# GPS_WATHER_STATION.net
KiCad netlist of a schematic drawn in Altium Designer
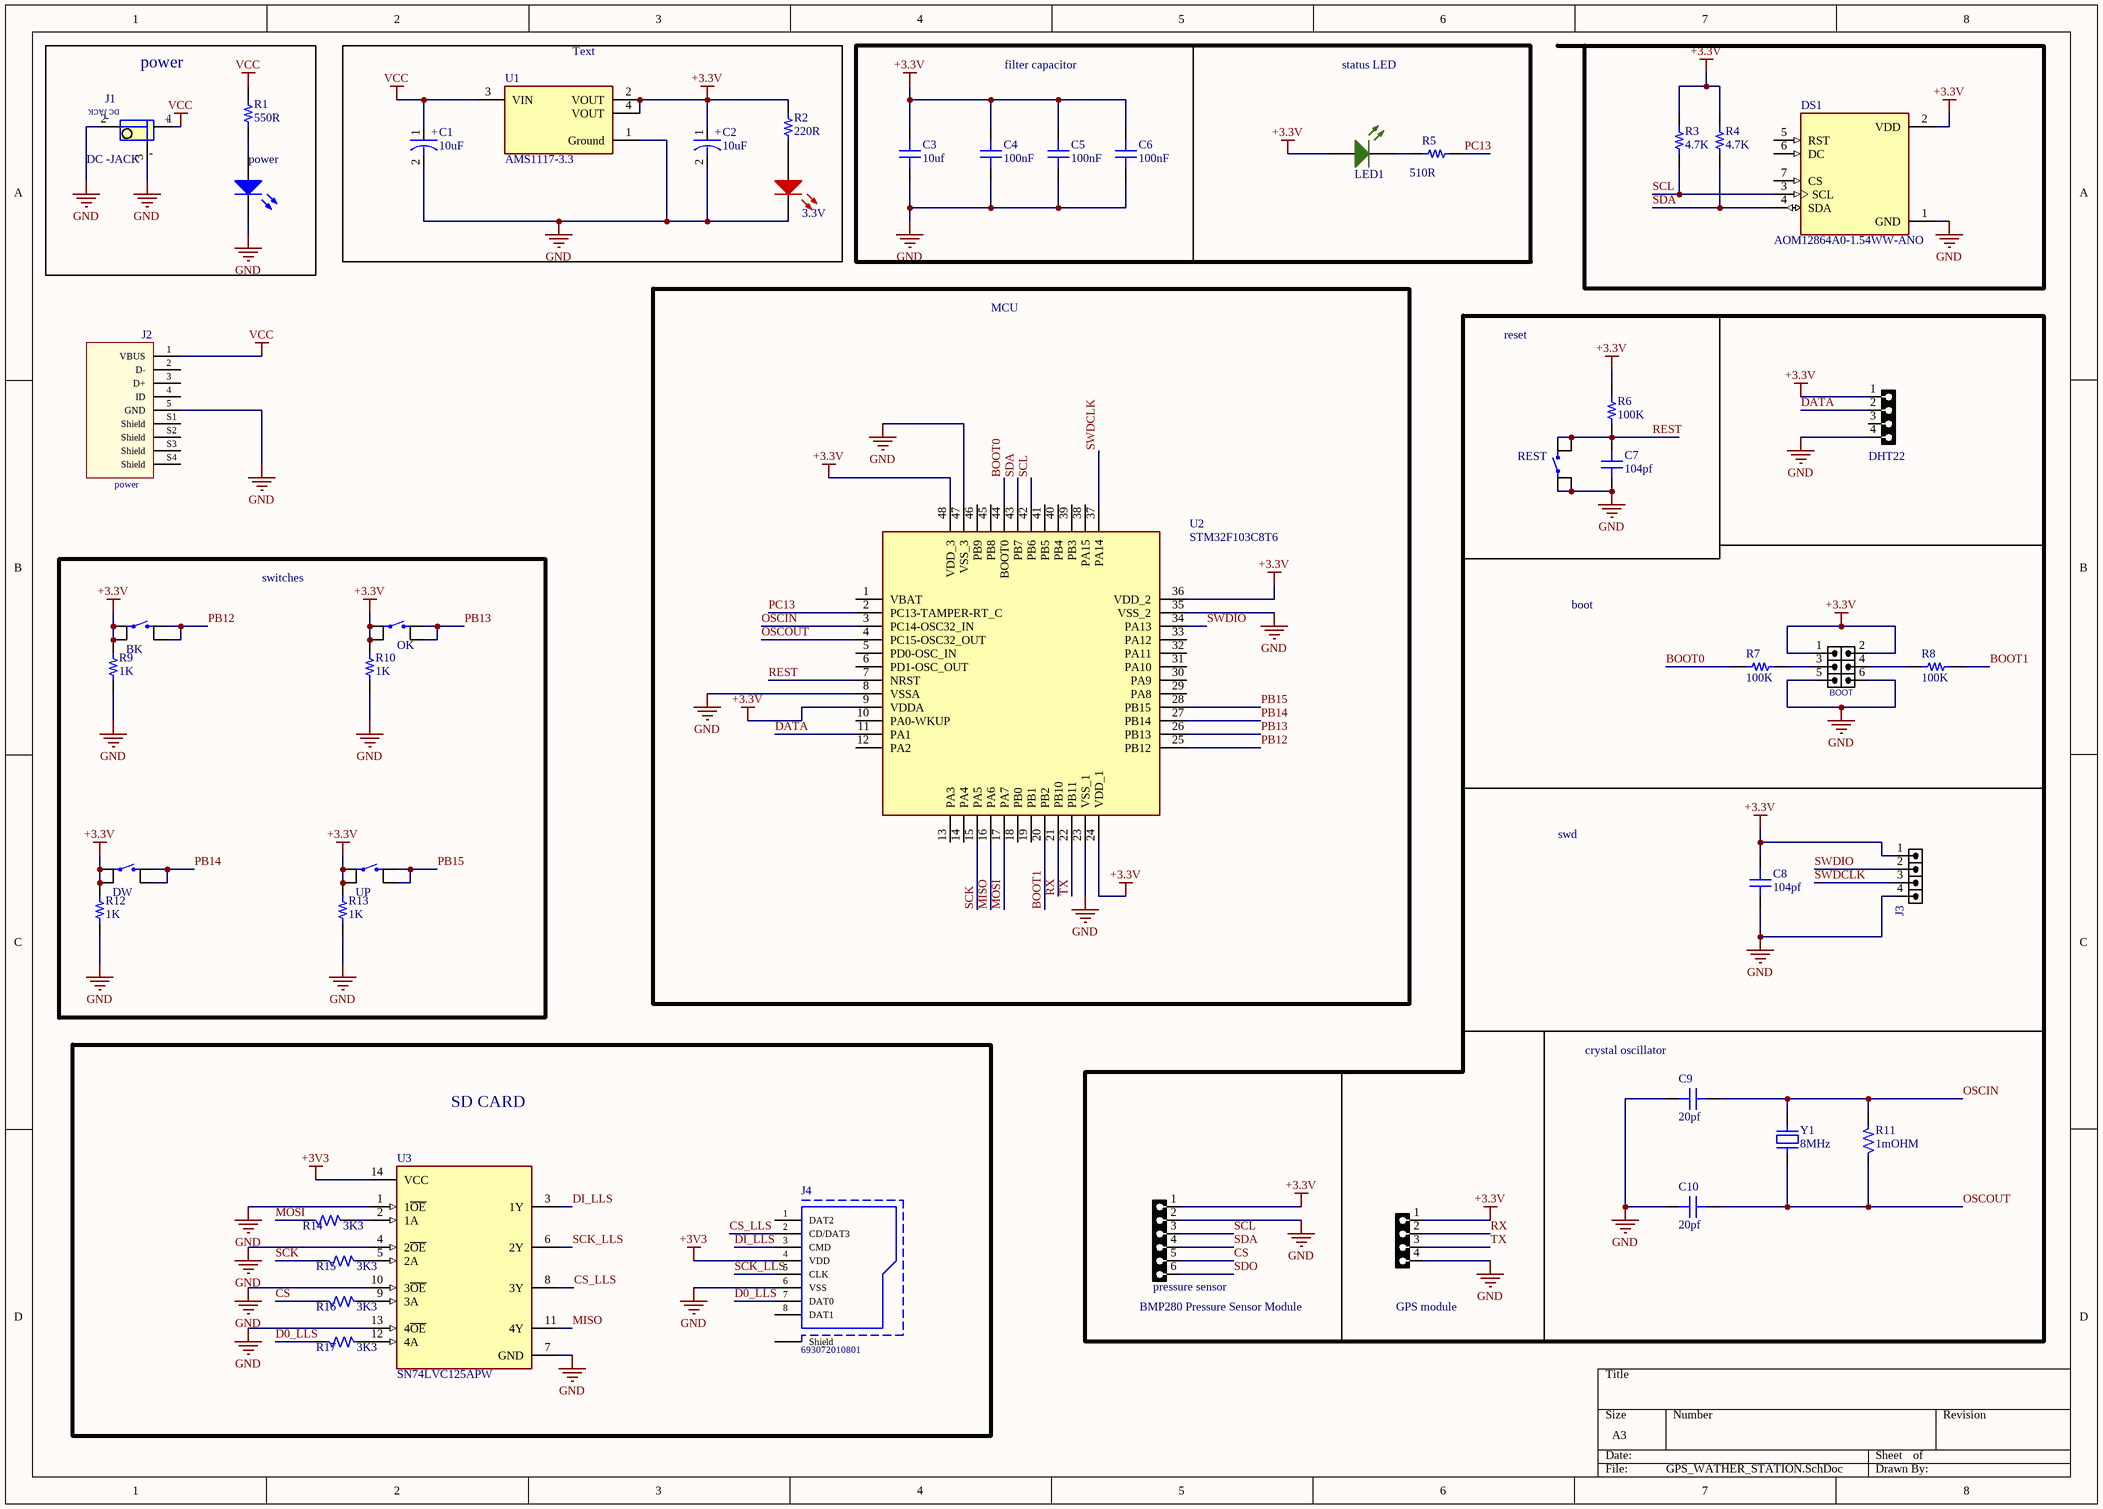
[diagram p0: GPS_WATHER_STATION.SchDoc]

(export (version "E")
  (design (tool "Eeschema 10.0.6"))
  (components
    (comp (ref "3.3V")
      (value "LED SMD 0603 RED")
      (footprint "LED_0603_BLUE")
      (libsource (lib "Led") (part "LED SMD 0603 RED"))
    )
    (comp (ref "BK")
      (value "Tactile 4PIN 6X6mm H4.5mm (SMD)")
      (footprint "SWPBS_SPDT_6X6X5")
      (description "Tactile Switch SPST-NO Top Actuated Surface Mount")
      (fields (field (name "PARTNUMBER") "PTS645SM43SMTR92 LFS"))
      (libsource (lib "Switch") (part "Tactile 4PIN 6X6mm H4.5mm (SMD)"))
    )
    (comp (ref "BOOT")
      (value "HDRM_2X3")
      (footprint "HDRS_M_2X3")
      (description "CONN, HEADER, Male, pitch: 2.54mm, 6POS, SMD")
      (fields (field (name "MANF_P#") "MANF_PART#") (field (name "MANF") "MANF"))
      (libsource (lib "Conn Header") (part "HDRS_M_2X3"))
    )
    (comp (ref "C1")
      (value "10uF")
      (footprint "CAP-T_1206")
      (description "10µF Molded Tantalum Capacitors 16V 1206 (3216 Metric) 3Ohm")
      (fields
        (field (name "MANUFACTURER") "AVX Corporation")
        (field (name "MANUFACTURER PART NUMBER") "TAJA106K016SNJ")
      )
      (libsource (lib "ESTEEMPCBLIB") (part "CAP-P_10uF-16V-10%-1206"))
    )
    (comp (ref "C2")
      (value "10uF")
      (footprint "CAP-T_1206")
      (description "10µF Molded Tantalum Capacitors 16V 1206 (3216 Metric) 3Ohm")
      (fields
        (field (name "MANUFACTURER") "AVX Corporation")
        (field (name "MANUFACTURER PART NUMBER") "TAJA106K016SNJ")
      )
      (libsource (lib "ESTEEMPCBLIB") (part "CAP-P_10uF-16V-10%-1206"))
    )
    (comp (ref "C3")
      (value "10uf")
      (footprint "CAP 0402_1005")
      (description "SMT Capacitor")
      (libsource (lib "Capacitor") (part "Cap 0402"))
    )
    (comp (ref "C4")
      (value "100nF")
      (footprint "CAP 0402_1005")
      (description "SMT Capacitor")
      (libsource (lib "Capacitor") (part "Cap 0402"))
    )
    (comp (ref "C5")
      (value "100nF")
      (footprint "CAP 0402_1005")
      (description "SMT Capacitor")
      (libsource (lib "Capacitor") (part "Cap 0402"))
    )
    (comp (ref "C6")
      (value "100nF")
      (footprint "CAP 0402_1005")
      (description "SMT Capacitor")
      (libsource (lib "Capacitor") (part "Cap 0402"))
    )
    (comp (ref "C7")
      (value "104pf")
      (footprint "CAP 0402_1005")
      (description "SMT Capacitor")
      (libsource (lib "Capacitor") (part "Cap 0402"))
    )
    (comp (ref "C8")
      (value "104pf")
      (footprint "CAP 0402_1005")
      (description "SMT Capacitor")
      (libsource (lib "Capacitor") (part "Cap 0402"))
    )
    (comp (ref "C9")
      (value "20pf")
      (footprint "CAP 0402_1005")
      (description "SMT Capacitor")
      (libsource (lib "Capacitor") (part "Cap 0402"))
    )
    (comp (ref "C10")
      (value "20pf")
      (footprint "CAP 0402_1005")
      (description "SMT Capacitor")
      (libsource (lib "Capacitor") (part "Cap 0402"))
    )
    (comp (ref "DHT22")
      (value "HDRF4")
      (footprint "HDRLP_F_1X4")
      (description "CONN, HEADER, Male, pitch: 2.54mm, 4POS")
      (libsource (lib "") (part "HDRLP_F_1X4_1"))
    )
    (comp (ref "DS1")
      (value "AOM12864A0-1.54WW-ANO")
      (footprint "LCD_AOM12864A0-1.54WW-ANO")
      (description "Non-Touch Graphic LCD Display Module - White OLED SPI 1.54 (39.12mm) 128 x 64")
      (fields (field (name "MF") "Orient Display"))
      (libsource (lib "AOM12864A0-1.54WW-ANO") (part "AOM12864A0-1.54WW-ANO"))
    )
    (comp (ref "DW")
      (value "Tactile 4PIN 6X6mm H4.5mm (SMD)")
      (footprint "SWPBS_SPDT_6X6X5")
      (description "Tactile Switch SPST-NO Top Actuated Surface Mount")
      (fields (field (name "PARTNUMBER") "PTS645SM43SMTR92 LFS"))
      (libsource (lib "Switch") (part "Tactile 4PIN 6X6mm H4.5mm (SMD)"))
    )
    (comp (ref "GPS module")
      (value "HDRF4")
      (footprint "HDRLP_F_1X4")
      (description "CONN, HEADER, Male, pitch: 2.54mm, 4POS")
      (libsource (lib "Conn Header") (part "HDRLP_F_1X4"))
    )
    (comp (ref "J1")
      (value "DC -JACK")
      (footprint "CON3_129_PJ-002A_TH_RA")
      (description "3 Pins, 1 Row 228mil Pitch, right angle Connector, male")
      (fields (field (name "MANUFACTURER") "JST") (field (name "MANUFACTURER PART NUMBER") "PJ-002A"))
      (libsource (lib "ESTEEMPCBLIB") (part "CON-PLG_3X1-228-DC_JACK"))
    )
    (comp (ref "J2")
      (value "power")
      (footprint "629105150521")
      (description "Micro USB 2.0 Type B Horizontal SMT 5 Contacts High Current WR-COM")
      (fields (field (name "PARTNUMBER") "629105150521") (field (name "PUBLISHER") "Wurth Elektronik"))
      (libsource (lib "Conn Usb") (part "Micro USB 2.0 Type B Horizontal (SMD) 629105150521"))
    )
    (comp (ref "J3")
      (value "HDR1X4")
      (footprint "HDRR_M_1X4")
      (description "CONN, HEADER, RightAngle, Male, pitch: 2.54mm, 4POS")
      (libsource (lib "Conn Header") (part "HDRR_M_1X4"))
    )
    (comp (ref "J4")
      (value "693072010801")
      (footprint "693072010801")
      (description "WR-CRD Micro SD Card Connector, Hinge Type")
      (fields (field (name "MANUFACTURER") "Wurth Elektronik") (field (name "PUBLISHER") "WurthElektronik"))
      (libsource (lib "Altium Content Vault") (part "WE-CN-SD-8-SW-1S"))
    )
    (comp (ref "LED1")
      (value "LED SMD 0603 GREEN")
      (footprint "LED_0603_GREEN")
      (libsource (lib "Led") (part "LED SMD 0603 GREEN"))
    )
    (comp (ref "OK")
      (value "Tactile 4PIN 6X6mm H4.5mm (SMD)")
      (footprint "SWPBS_SPDT_6X6X5")
      (description "Tactile Switch SPST-NO Top Actuated Surface Mount")
      (fields (field (name "PARTNUMBER") "PTS645SM43SMTR92 LFS"))
      (libsource (lib "Switch") (part "Tactile 4PIN 6X6mm H4.5mm (SMD)"))
    )
    (comp (ref "power")
      (value "LED SMD 0603 BLUE")
      (footprint "LED_0603_RED")
      (libsource (lib "Led") (part "LED SMD 0603 BLUE"))
    )
    (comp (ref "pressure sensor")
      (value "HDRF6")
      (footprint "HDRLP_F_1X6")
      (description "CONN, HEADER, Male, pitch: 2.54mm, 6POS")
      (libsource (lib "Conn Header") (part "HDRLP_F_1X6"))
    )
    (comp (ref "R1")
      (value "550R")
      (footprint "RES 0402_1005")
      (description "SMT Resistor")
      (libsource (lib "Resistor") (part "Res 0402"))
    )
    (comp (ref "R2")
      (value "220R")
      (footprint "RES 0402_1005")
      (description "SMT Resistor")
      (libsource (lib "Resistor") (part "Res 0402"))
    )
    (comp (ref "R3")
      (value "4.7K")
      (footprint "RES 0402_1005")
      (description "SMT Resistor")
      (libsource (lib "Resistor") (part "Res 0402"))
    )
    (comp (ref "R4")
      (value "4.7K")
      (footprint "RES 0402_1005")
      (description "SMT Resistor")
      (libsource (lib "Resistor") (part "Res 0402"))
    )
    (comp (ref "R5")
      (value "510R")
      (footprint "RES 0402_1005")
      (description "SMT Resistor")
      (libsource (lib "Resistor") (part "Res 0402"))
    )
    (comp (ref "R6")
      (value "100K")
      (footprint "RES 0402_1005")
      (description "SMT Resistor")
      (libsource (lib "Resistor") (part "Res 0402"))
    )
    (comp (ref "R7")
      (value "100K")
      (footprint "RES 0402_1005")
      (description "SMT Resistor")
      (libsource (lib "Resistor") (part "Res 0402"))
    )
    (comp (ref "R8")
      (value "100K")
      (footprint "RES 0402_1005")
      (description "SMT Resistor")
      (libsource (lib "Resistor") (part "Res 0402"))
    )
    (comp (ref "R9")
      (value "1K")
      (footprint "RES 0402_1005")
      (description "SMT Resistor")
      (libsource (lib "Resistor") (part "Res 0402"))
    )
    (comp (ref "R10")
      (value "1K")
      (footprint "RES 0402_1005")
      (description "SMT Resistor")
      (libsource (lib "Resistor") (part "Res 0402"))
    )
    (comp (ref "R11")
      (value "1mOHM")
      (footprint "RES_0805")
      (description "1.02 MOhms ±0.25% 0.125W, 1/8W Chip Resistor 0805 (2012 Metric) Thin Film")
      (fields
        (field (name "MANUFACTURER") "Vishay Dale")
        (field (name "MANUFACTURER PART NUMBER") "RT0805CRE071M02L")
      )
      (libsource (lib "ESTEEMPCBLIB") (part "RES_1mOHM-0.125W-0.25%-0805"))
    )
    (comp (ref "R12")
      (value "1K")
      (footprint "RES 0402_1005")
      (description "SMT Resistor")
      (libsource (lib "Resistor") (part "Res 0402"))
    )
    (comp (ref "R13")
      (value "1K")
      (footprint "RES 0402_1005")
      (description "SMT Resistor")
      (libsource (lib "Resistor") (part "Res 0402"))
    )
    (comp (ref "R14")
      (value "3K3")
      (footprint "RES_0603")
      (description "3.3 kOhms ±1% 0.1W, 1/10W Chip Resistor 0603 (1608 Metric) Automotive AEC-Q200 Thick Film")
      (fields (field (name "MANUFACTURER") "Wilson") (field (name "MANUFACTURER PART NUMBER") "WR06X3301FTL"))
      (libsource (lib "ESTEEMPCBLIB") (part "RES_3.3K-0.1W-1%-0603"))
    )
    (comp (ref "R15")
      (value "3K3")
      (footprint "RES_0603")
      (description "3.3 kOhms ±1% 0.1W, 1/10W Chip Resistor 0603 (1608 Metric) Automotive AEC-Q200 Thick Film")
      (fields (field (name "MANUFACTURER") "Wilson") (field (name "MANUFACTURER PART NUMBER") "WR06X3301FTL"))
      (libsource (lib "ESTEEMPCBLIB") (part "RES_3.3K-0.1W-1%-0603"))
    )
    (comp (ref "R16")
      (value "3K3")
      (footprint "RES_0603")
      (description "3.3 kOhms ±1% 0.1W, 1/10W Chip Resistor 0603 (1608 Metric) Automotive AEC-Q200 Thick Film")
      (fields (field (name "MANUFACTURER") "Wilson") (field (name "MANUFACTURER PART NUMBER") "WR06X3301FTL"))
      (libsource (lib "ESTEEMPCBLIB") (part "RES_3.3K-0.1W-1%-0603"))
    )
    (comp (ref "R17")
      (value "3K3")
      (footprint "RES_0603")
      (description "3.3 kOhms ±1% 0.1W, 1/10W Chip Resistor 0603 (1608 Metric) Automotive AEC-Q200 Thick Film")
      (fields (field (name "MANUFACTURER") "Wilson") (field (name "MANUFACTURER PART NUMBER") "WR06X3301FTL"))
      (libsource (lib "ESTEEMPCBLIB") (part "RES_3.3K-0.1W-1%-0603"))
    )
    (comp (ref "REST")
      (value "Tactile 4PIN 6X6mm H4.5mm (SMD)")
      (footprint "SWPBS_SPDT_6X6X5")
      (description "Tactile Switch SPST-NO Top Actuated Surface Mount")
      (fields (field (name "PARTNUMBER") "PTS645SM43SMTR92 LFS"))
      (libsource (lib "Switch") (part "Tactile 4PIN 6X6mm H4.5mm (SMD)"))
    )
    (comp (ref "U1")
      (value "AMS1117-3.3")
      (footprint "FP-AMS1117-IPC_C")
      (description "LDO Voltage Regulators 1A, 3.3V")
      (fields
        (field (name "OCTOPART") "https://octopart.com/ams1117-3.3-advanced+monolithic+systems-25899300")
        (field (name "MANUFACTURER") "Advanced Monolithic Systems")
      )
      (libsource (lib "Altium Content Vault") (part "8bdbb5f8e77002000e30dd2845d0354"))
    )
    (comp (ref "U2")
      (value "STM32F103C8T6")
      (footprint "LQFP-48_19.6_393_58X11_SMD")
      (description "ARM® Cortex®-M3 STM32F1 Microcontroller IC 32-Bit 72MHz 64KB (64K x 8) FLASH 48-LQFP (7x7)")
      (fields (field (name "MANUFACTURER") "STMicroelectronics"))
      (libsource (lib "ESTEEMPCBLIB") (part "IC_STM32F103C8T6"))
    )
    (comp (ref "U3")
      (value "SN74LVC125APW")
      (footprint "FP-PW0014A-IPC_C")
      (description "IC BUF NON-INVERT 3.6V 14TSSOP")
      (libsource (lib "Altium Content Vault") (part "54a0314e8388b38398c6e2b071dda32"))
    )
    (comp (ref "UP")
      (value "Tactile 4PIN 6X6mm H4.5mm (SMD)")
      (footprint "SWPBS_SPDT_6X6X5")
      (description "Tactile Switch SPST-NO Top Actuated Surface Mount")
      (fields (field (name "PARTNUMBER") "PTS645SM43SMTR92 LFS"))
      (libsource (lib "Switch") (part "Tactile 4PIN 6X6mm H4.5mm (SMD)"))
    )
    (comp (ref "Y1")
      (value "8MHz")
      (footprint "HC-49S SMD")
      (description "SMT Crystal")
      (fields (field (name "PARTNUMBER") "ABLS-8.000MHZ-K4T"))
      (libsource (lib "Xtal") (part "Crystal HC-49S SMD 8MHz"))
    )
  )
  (nets
    (net (code "1") (name "+3.3V") (class "Default")
      (node (ref "BK") (pin "1") (pinfunction "1_1") (pintype "passive"))
      (node (ref "BK") (pin "4") (pinfunction "4_4") (pintype "passive"))
      (node (ref "BOOT") (pin "1") (pinfunction "1_1") (pintype "passive"))
      (node (ref "BOOT") (pin "2") (pinfunction "2_2") (pintype "passive"))
      (node (ref "C2") (pin "1") (pinfunction "1_1") (pintype "passive"))
      (node (ref "C3") (pin "2") (pinfunction "2_2") (pintype "passive"))
      (node (ref "C4") (pin "2") (pinfunction "2_2") (pintype "passive"))
      (node (ref "C5") (pin "2") (pinfunction "2_2") (pintype "passive"))
      (node (ref "C6") (pin "2") (pinfunction "2_2") (pintype "passive"))
      (node (ref "C8") (pin "2") (pinfunction "2_2") (pintype "passive"))
      (node (ref "DHT22") (pin "1") (pinfunction "1_1") (pintype "passive"))
      (node (ref "DS1") (pin "2") (pinfunction "VDD_2") (pintype "power_in"))
      (node (ref "DW") (pin "1") (pinfunction "1_1") (pintype "passive"))
      (node (ref "DW") (pin "4") (pinfunction "4_4") (pintype "passive"))
      (node (ref "GPS module") (pin "1") (pinfunction "1_1") (pintype "passive"))
      (node (ref "J3") (pin "1") (pinfunction "1_1") (pintype "passive"))
      (node (ref "LED1") (pin "1") (pinfunction "A_1") (pintype "passive"))
      (node (ref "OK") (pin "1") (pinfunction "1_1") (pintype "passive"))
      (node (ref "OK") (pin "4") (pinfunction "4_4") (pintype "passive"))
      (node (ref "R10") (pin "2") (pinfunction "2_2") (pintype "passive"))
      (node (ref "R12") (pin "2") (pinfunction "2_2") (pintype "passive"))
      (node (ref "R13") (pin "2") (pinfunction "2_2") (pintype "passive"))
      (node (ref "R2") (pin "2") (pinfunction "2_2") (pintype "passive"))
      (node (ref "R3") (pin "2") (pinfunction "2_2") (pintype "passive"))
      (node (ref "R4") (pin "2") (pinfunction "2_2") (pintype "passive"))
      (node (ref "R6") (pin "1") (pinfunction "1_1") (pintype "passive"))
      (node (ref "R9") (pin "2") (pinfunction "2_2") (pintype "passive"))
      (node (ref "U1") (pin "2") (pinfunction "VOUT_2") (pintype "passive"))
      (node (ref "U1") (pin "4") (pinfunction "VOUT_4") (pintype "passive"))
      (node (ref "U2") (pin "24") (pinfunction "VDD_1_24") (pintype "passive"))
      (node (ref "U2") (pin "36") (pinfunction "VDD_2_36") (pintype "passive"))
      (node (ref "U2") (pin "48") (pinfunction "VDD_3_48") (pintype "passive"))
      (node (ref "U2") (pin "9") (pinfunction "VDDA_9") (pintype "passive"))
      (node (ref "UP") (pin "1") (pinfunction "1_1") (pintype "passive"))
      (node (ref "UP") (pin "4") (pinfunction "4_4") (pintype "passive"))
      (node (ref "pressure sensor") (pin "1") (pinfunction "1_1") (pintype "passive"))
    )
    (net (code "2") (name "+3V3") (class "Default")
      (node (ref "J4") (pin "4") (pinfunction "VDD_4") (pintype "passive"))
      (node (ref "U3") (pin "14") (pinfunction "VCC_14") (pintype "power_in"))
    )
    (net (code "3") (name "/BOOT0") (class "Default")
      (node (ref "R7") (pin "2") (pinfunction "2_2") (pintype "passive"))
      (node (ref "U2") (pin "44") (pinfunction "BOOT0_44") (pintype "passive"))
    )
    (net (code "4") (name "/BOOT1") (class "Default")
      (node (ref "R8") (pin "1") (pinfunction "1_1") (pintype "passive"))
      (node (ref "U2") (pin "20") (pinfunction "PB2_20") (pintype "passive"))
    )
    (net (code "5") (name "/CS") (class "Default")
      (node (ref "R16") (pin "1") (pinfunction "1_1") (pintype "passive"))
      (node (ref "pressure sensor") (pin "5") (pinfunction "5_5") (pintype "passive"))
    )
    (net (code "6") (name "/CS_LLS") (class "Default")
      (node (ref "J4") (pin "2") (pinfunction "CD/DAT3_2") (pintype "passive"))
      (node (ref "U3") (pin "8") (pinfunction "3Y_8") (pintype "tri_state"))
    )
    (net (code "7") (name "/D0_LLS") (class "Default")
      (node (ref "J4") (pin "7") (pinfunction "DAT0_7") (pintype "passive"))
      (node (ref "R17") (pin "1") (pinfunction "1_1") (pintype "passive"))
    )
    (net (code "8") (name "/DATA") (class "Default")
      (node (ref "DHT22") (pin "2") (pinfunction "2_2") (pintype "passive"))
      (node (ref "U2") (pin "11") (pinfunction "PA1_11") (pintype "passive"))
    )
    (net (code "9") (name "/DI_LLS") (class "Default")
      (node (ref "J4") (pin "3") (pinfunction "CMD_3") (pintype "passive"))
      (node (ref "U3") (pin "3") (pinfunction "1Y_3") (pintype "tri_state"))
    )
    (net (code "10") (name "/MISO") (class "Default")
      (node (ref "U2") (pin "16") (pinfunction "PA6_16") (pintype "passive"))
      (node (ref "U3") (pin "11") (pinfunction "4Y_11") (pintype "tri_state"))
    )
    (net (code "11") (name "/MOSI") (class "Default")
      (node (ref "R14") (pin "1") (pinfunction "1_1") (pintype "passive"))
      (node (ref "U2") (pin "17") (pinfunction "PA7_17") (pintype "passive"))
    )
    (net (code "12") (name "/OSCIN") (class "Default")
      (node (ref "C9") (pin "1") (pinfunction "1_1") (pintype "passive"))
      (node (ref "R11") (pin "2") (pinfunction "2_2") (pintype "passive"))
      (node (ref "U2") (pin "3") (pinfunction "PC14-OSC32_IN_3") (pintype "passive"))
      (node (ref "Y1") (pin "2") (pinfunction "2_2") (pintype "passive"))
    )
    (net (code "13") (name "/OSCOUT") (class "Default")
      (node (ref "C10") (pin "1") (pinfunction "1_1") (pintype "passive"))
      (node (ref "R11") (pin "1") (pinfunction "1_1") (pintype "passive"))
      (node (ref "U2") (pin "4") (pinfunction "PC15-OSC32_OUT_4") (pintype "passive"))
      (node (ref "Y1") (pin "1") (pinfunction "1_1") (pintype "passive"))
    )
    (net (code "14") (name "/PB12") (class "Default")
      (node (ref "BK") (pin "2") (pinfunction "2_2") (pintype "passive"))
      (node (ref "BK") (pin "3") (pinfunction "3_3") (pintype "passive"))
      (node (ref "U2") (pin "25") (pinfunction "PB12_25") (pintype "passive"))
    )
    (net (code "15") (name "/PB13") (class "Default")
      (node (ref "OK") (pin "2") (pinfunction "2_2") (pintype "passive"))
      (node (ref "OK") (pin "3") (pinfunction "3_3") (pintype "passive"))
      (node (ref "U2") (pin "26") (pinfunction "PB13_26") (pintype "passive"))
    )
    (net (code "16") (name "/PB14") (class "Default")
      (node (ref "DW") (pin "2") (pinfunction "2_2") (pintype "passive"))
      (node (ref "DW") (pin "3") (pinfunction "3_3") (pintype "passive"))
      (node (ref "U2") (pin "27") (pinfunction "PB14_27") (pintype "passive"))
    )
    (net (code "17") (name "/PB15") (class "Default")
      (node (ref "U2") (pin "28") (pinfunction "PB15_28") (pintype "passive"))
      (node (ref "UP") (pin "2") (pinfunction "2_2") (pintype "passive"))
      (node (ref "UP") (pin "3") (pinfunction "3_3") (pintype "passive"))
    )
    (net (code "18") (name "/PC13") (class "Default")
      (node (ref "R5") (pin "1") (pinfunction "1_1") (pintype "passive"))
      (node (ref "U2") (pin "2") (pinfunction "PC13-TAMPER-RT_C_2") (pintype "passive"))
    )
    (net (code "19") (name "/REST") (class "Default")
      (node (ref "C7") (pin "2") (pinfunction "2_2") (pintype "passive"))
      (node (ref "R6") (pin "2") (pinfunction "2_2") (pintype "passive"))
      (node (ref "REST") (pin "2") (pinfunction "2_2") (pintype "passive"))
      (node (ref "REST") (pin "3") (pinfunction "3_3") (pintype "passive"))
      (node (ref "U2") (pin "7") (pinfunction "NRST_7") (pintype "passive"))
    )
    (net (code "20") (name "/RX") (class "Default")
      (node (ref "GPS module") (pin "2") (pinfunction "2_2") (pintype "passive"))
      (node (ref "U2") (pin "21") (pinfunction "PB10_21") (pintype "passive"))
    )
    (net (code "21") (name "/SCK") (class "Default")
      (node (ref "R15") (pin "1") (pinfunction "1_1") (pintype "passive"))
      (node (ref "U2") (pin "15") (pinfunction "PA5_15") (pintype "passive"))
    )
    (net (code "22") (name "/SCK_LLS") (class "Default")
      (node (ref "J4") (pin "5") (pinfunction "CLK_5") (pintype "passive"))
      (node (ref "U3") (pin "6") (pinfunction "2Y_6") (pintype "tri_state"))
    )
    (net (code "23") (name "/SCL") (class "Default")
      (node (ref "DS1") (pin "3") (pinfunction "SCL_3") (pintype "input"))
      (node (ref "R3") (pin "1") (pinfunction "1_1") (pintype "passive"))
      (node (ref "U2") (pin "42") (pinfunction "PB6_42") (pintype "passive"))
      (node (ref "pressure sensor") (pin "3") (pinfunction "3_3") (pintype "passive"))
    )
    (net (code "24") (name "/SDA") (class "Default")
      (node (ref "DS1") (pin "4") (pinfunction "SDA_4") (pintype "bidirectional"))
      (node (ref "R4") (pin "1") (pinfunction "1_1") (pintype "passive"))
      (node (ref "U2") (pin "43") (pinfunction "PB7_43") (pintype "passive"))
      (node (ref "pressure sensor") (pin "4") (pinfunction "4_4") (pintype "passive"))
    )
    (net (code "25") (name "/SDO") (class "Default")
      (node (ref "pressure sensor") (pin "6") (pinfunction "6_6") (pintype "passive"))
    )
    (net (code "26") (name "/SWDCLK") (class "Default")
      (node (ref "J3") (pin "3") (pinfunction "3_3") (pintype "passive"))
      (node (ref "U2") (pin "37") (pinfunction "PA14_37") (pintype "passive"))
    )
    (net (code "27") (name "/SWDIO") (class "Default")
      (node (ref "J3") (pin "2") (pinfunction "2_2") (pintype "passive"))
      (node (ref "U2") (pin "34") (pinfunction "PA13_34") (pintype "passive"))
    )
    (net (code "28") (name "/TX") (class "Default")
      (node (ref "GPS module") (pin "3") (pinfunction "3_3") (pintype "passive"))
      (node (ref "U2") (pin "22") (pinfunction "PB11_22") (pintype "passive"))
    )
    (net (code "29") (name "GND") (class "Default")
      (node (ref "3.3V") (pin "2") (pinfunction "K_2") (pintype "passive"))
      (node (ref "BOOT") (pin "5") (pinfunction "5_5") (pintype "passive"))
      (node (ref "BOOT") (pin "6") (pinfunction "6_6") (pintype "passive"))
      (node (ref "C1") (pin "2") (pinfunction "2_2") (pintype "passive"))
      (node (ref "C10") (pin "2") (pinfunction "2_2") (pintype "passive"))
      (node (ref "C2") (pin "2") (pinfunction "2_2") (pintype "passive"))
      (node (ref "C3") (pin "1") (pinfunction "1_1") (pintype "passive"))
      (node (ref "C4") (pin "1") (pinfunction "1_1") (pintype "passive"))
      (node (ref "C5") (pin "1") (pinfunction "1_1") (pintype "passive"))
      (node (ref "C6") (pin "1") (pinfunction "1_1") (pintype "passive"))
      (node (ref "C7") (pin "1") (pinfunction "1_1") (pintype "passive"))
      (node (ref "C8") (pin "1") (pinfunction "1_1") (pintype "passive"))
      (node (ref "C9") (pin "2") (pinfunction "2_2") (pintype "passive"))
      (node (ref "DHT22") (pin "4") (pinfunction "4_4") (pintype "passive"))
      (node (ref "DS1") (pin "1") (pinfunction "GND_1") (pintype "power_in"))
      (node (ref "GPS module") (pin "4") (pinfunction "4_4") (pintype "passive"))
      (node (ref "J1") (pin "2") (pinfunction "2_2") (pintype "passive"))
      (node (ref "J1") (pin "3") (pinfunction "-_3") (pintype "passive"))
      (node (ref "J2") (pin "5") (pinfunction "GND_5") (pintype "passive"))
      (node (ref "J3") (pin "4") (pinfunction "4_4") (pintype "passive"))
      (node (ref "J4") (pin "6") (pinfunction "VSS_6") (pintype "passive"))
      (node (ref "R10") (pin "1") (pinfunction "1_1") (pintype "passive"))
      (node (ref "R12") (pin "1") (pinfunction "1_1") (pintype "passive"))
      (node (ref "R13") (pin "1") (pinfunction "1_1") (pintype "passive"))
      (node (ref "R9") (pin "1") (pinfunction "1_1") (pintype "passive"))
      (node (ref "REST") (pin "1") (pinfunction "1_1") (pintype "passive"))
      (node (ref "REST") (pin "4") (pinfunction "4_4") (pintype "passive"))
      (node (ref "U1") (pin "1") (pinfunction "Ground_1") (pintype "power_in"))
      (node (ref "U2") (pin "23") (pinfunction "VSS_1_23") (pintype "passive"))
      (node (ref "U2") (pin "35") (pinfunction "VSS_2_35") (pintype "passive"))
      (node (ref "U2") (pin "47") (pinfunction "VSS_3_47") (pintype "passive"))
      (node (ref "U2") (pin "8") (pinfunction "VSSA_8") (pintype "passive"))
      (node (ref "U3") (pin "1") (pinfunction "1~{OE}_1") (pintype "input"))
      (node (ref "U3") (pin "10") (pinfunction "3~{OE}_10") (pintype "input"))
      (node (ref "U3") (pin "13") (pinfunction "4~{OE}_13") (pintype "input"))
      (node (ref "U3") (pin "4") (pinfunction "2~{OE}_4") (pintype "input"))
      (node (ref "U3") (pin "7") (pinfunction "GND_7") (pintype "power_in"))
      (node (ref "power") (pin "2") (pinfunction "K_2") (pintype "passive"))
      (node (ref "pressure sensor") (pin "2") (pinfunction "2_2") (pintype "passive"))
    )
    (net (code "30") (name "Net-(3.3V-A)") (class "Default")
      (node (ref "3.3V") (pin "1") (pinfunction "A_1") (pintype "passive"))
      (node (ref "R2") (pin "1") (pinfunction "1_1") (pintype "passive"))
    )
    (net (code "31") (name "Net-(BOOT-Pad3)") (class "Default")
      (node (ref "BOOT") (pin "3") (pinfunction "3_3") (pintype "passive"))
      (node (ref "R7") (pin "1") (pinfunction "1_1") (pintype "passive"))
    )
    (net (code "32") (name "Net-(BOOT-Pad4)") (class "Default")
      (node (ref "BOOT") (pin "4") (pinfunction "4_4") (pintype "passive"))
      (node (ref "R8") (pin "2") (pinfunction "2_2") (pintype "passive"))
    )
    (net (code "33") (name "Net-(LED1-K)") (class "Default")
      (node (ref "LED1") (pin "2") (pinfunction "K_2") (pintype "passive"))
      (node (ref "R5") (pin "2") (pinfunction "2_2") (pintype "passive"))
    )
    (net (code "34") (name "Net-(U3-1A)") (class "Default")
      (node (ref "R14") (pin "2") (pinfunction "2_2") (pintype "passive"))
      (node (ref "U3") (pin "2") (pinfunction "1A_2") (pintype "input"))
    )
    (net (code "35") (name "Net-(U3-2A)") (class "Default")
      (node (ref "R15") (pin "2") (pinfunction "2_2") (pintype "passive"))
      (node (ref "U3") (pin "5") (pinfunction "2A_5") (pintype "input"))
    )
    (net (code "36") (name "Net-(U3-3A)") (class "Default")
      (node (ref "R16") (pin "2") (pinfunction "2_2") (pintype "passive"))
      (node (ref "U3") (pin "9") (pinfunction "3A_9") (pintype "input"))
    )
    (net (code "37") (name "Net-(U3-4A)") (class "Default")
      (node (ref "R17") (pin "2") (pinfunction "2_2") (pintype "passive"))
      (node (ref "U3") (pin "12") (pinfunction "4A_12") (pintype "input"))
    )
    (net (code "38") (name "Net-(power-A)") (class "Default")
      (node (ref "R1") (pin "1") (pinfunction "1_1") (pintype "passive"))
      (node (ref "power") (pin "1") (pinfunction "A_1") (pintype "passive"))
    )
    (net (code "39") (name "VCC") (class "Default")
      (node (ref "C1") (pin "1") (pinfunction "1_1") (pintype "passive"))
      (node (ref "J1") (pin "1") (pinfunction "1_1") (pintype "passive"))
      (node (ref "J2") (pin "1") (pinfunction "VBUS_1") (pintype "passive"))
      (node (ref "R1") (pin "2") (pinfunction "2_2") (pintype "passive"))
      (node (ref "U1") (pin "3") (pinfunction "VIN_3") (pintype "power_in"))
    )
    (net (code "40") (name "unconnected-(DHT22-Pad3)") (class "Default")
      (node (ref "DHT22") (pin "3") (pinfunction "3_3") (pintype "passive"))
    )
    (net (code "41") (name "unconnected-(DS1-CS-Pad7)") (class "Default")
      (node (ref "DS1") (pin "7") (pinfunction "CS_7") (pintype "input"))
    )
    (net (code "42") (name "unconnected-(DS1-DC-Pad6)") (class "Default")
      (node (ref "DS1") (pin "6") (pinfunction "DC_6") (pintype "input"))
    )
    (net (code "43") (name "unconnected-(DS1-RST-Pad5)") (class "Default")
      (node (ref "DS1") (pin "5") (pinfunction "RST_5") (pintype "input"))
    )
    (net (code "44") (name "unconnected-(J2-D+-Pad3)") (class "Default")
      (node (ref "J2") (pin "3") (pinfunction "D+_3") (pintype "passive"))
    )
    (net (code "45") (name "unconnected-(J2-D--Pad2)") (class "Default")
      (node (ref "J2") (pin "2") (pinfunction "D-_2") (pintype "passive"))
    )
    (net (code "46") (name "unconnected-(J2-ID-Pad4)") (class "Default")
      (node (ref "J2") (pin "4") (pinfunction "ID_4") (pintype "passive"))
    )
    (net (code "47") (name "unconnected-(J2-Shield-PadS1)") (class "Default")
      (node (ref "J2") (pin "S1") (pinfunction "Shield_S1") (pintype "passive"))
    )
    (net (code "48") (name "unconnected-(J2-Shield-PadS2)") (class "Default")
      (node (ref "J2") (pin "S2") (pinfunction "Shield_S2") (pintype "passive"))
    )
    (net (code "49") (name "unconnected-(J2-Shield-PadS3)") (class "Default")
      (node (ref "J2") (pin "S3") (pinfunction "Shield_S3") (pintype "passive"))
    )
    (net (code "50") (name "unconnected-(J2-Shield-PadS4)") (class "Default")
      (node (ref "J2") (pin "S4") (pinfunction "Shield_S4") (pintype "passive"))
    )
    (net (code "51") (name "unconnected-(J4-DAT1-Pad8)") (class "Default")
      (node (ref "J4") (pin "8") (pinfunction "DAT1_8") (pintype "passive"))
    )
    (net (code "52") (name "unconnected-(J4-DAT2-Pad1)") (class "Default")
      (node (ref "J4") (pin "1") (pinfunction "DAT2_1") (pintype "passive"))
    )
    (net (code "53") (name "unconnected-(J4-PadShield)") (class "Default")
      (node (ref "J4") (pin "Shield") (pinfunction "Shield_Shield") (pintype "passive"))
    )
    (net (code "54") (name "unconnected-(U2-PA0-WKUP-Pad10)") (class "Default")
      (node (ref "U2") (pin "10") (pinfunction "PA0-WKUP_10") (pintype "passive"))
    )
    (net (code "55") (name "unconnected-(U2-PA2-Pad12)") (class "Default")
      (node (ref "U2") (pin "12") (pinfunction "PA2_12") (pintype "passive"))
    )
    (net (code "56") (name "unconnected-(U2-PA3-Pad13)") (class "Default")
      (node (ref "U2") (pin "13") (pinfunction "PA3_13") (pintype "passive"))
    )
    (net (code "57") (name "unconnected-(U2-PA4-Pad14)") (class "Default")
      (node (ref "U2") (pin "14") (pinfunction "PA4_14") (pintype "passive"))
    )
    (net (code "58") (name "unconnected-(U2-PA8-Pad29)") (class "Default")
      (node (ref "U2") (pin "29") (pinfunction "PA8_29") (pintype "passive"))
    )
    (net (code "59") (name "unconnected-(U2-PA9-Pad30)") (class "Default")
      (node (ref "U2") (pin "30") (pinfunction "PA9_30") (pintype "passive"))
    )
    (net (code "60") (name "unconnected-(U2-PA10-Pad31)") (class "Default")
      (node (ref "U2") (pin "31") (pinfunction "PA10_31") (pintype "passive"))
    )
    (net (code "61") (name "unconnected-(U2-PA11-Pad32)") (class "Default")
      (node (ref "U2") (pin "32") (pinfunction "PA11_32") (pintype "passive"))
    )
    (net (code "62") (name "unconnected-(U2-PA12-Pad33)") (class "Default")
      (node (ref "U2") (pin "33") (pinfunction "PA12_33") (pintype "passive"))
    )
    (net (code "63") (name "unconnected-(U2-PA15-Pad38)") (class "Default")
      (node (ref "U2") (pin "38") (pinfunction "PA15_38") (pintype "passive"))
    )
    (net (code "64") (name "unconnected-(U2-PB0-Pad18)") (class "Default")
      (node (ref "U2") (pin "18") (pinfunction "PB0_18") (pintype "passive"))
    )
    (net (code "65") (name "unconnected-(U2-PB1-Pad19)") (class "Default")
      (node (ref "U2") (pin "19") (pinfunction "PB1_19") (pintype "passive"))
    )
    (net (code "66") (name "unconnected-(U2-PB3-Pad39)") (class "Default")
      (node (ref "U2") (pin "39") (pinfunction "PB3_39") (pintype "passive"))
    )
    (net (code "67") (name "unconnected-(U2-PB4-Pad40)") (class "Default")
      (node (ref "U2") (pin "40") (pinfunction "PB4_40") (pintype "passive"))
    )
    (net (code "68") (name "unconnected-(U2-PB5-Pad41)") (class "Default")
      (node (ref "U2") (pin "41") (pinfunction "PB5_41") (pintype "passive"))
    )
    (net (code "69") (name "unconnected-(U2-PB8-Pad45)") (class "Default")
      (node (ref "U2") (pin "45") (pinfunction "PB8_45") (pintype "passive"))
    )
    (net (code "70") (name "unconnected-(U2-PB9-Pad46)") (class "Default")
      (node (ref "U2") (pin "46") (pinfunction "PB9_46") (pintype "passive"))
    )
    (net (code "71") (name "unconnected-(U2-PD0-OSC_IN-Pad5)") (class "Default")
      (node (ref "U2") (pin "5") (pinfunction "PD0-OSC_IN_5") (pintype "passive"))
    )
    (net (code "72") (name "unconnected-(U2-PD1-OSC_OUT-Pad6)") (class "Default")
      (node (ref "U2") (pin "6") (pinfunction "PD1-OSC_OUT_6") (pintype "passive"))
    )
    (net (code "73") (name "unconnected-(U2-VBAT-Pad1)") (class "Default")
      (node (ref "U2") (pin "1") (pinfunction "VBAT_1") (pintype "passive"))
    )
  )
)
